# trackuino_sensor_mk2_chip.net
KiCad netlist of a schematic drawn in EAGLE
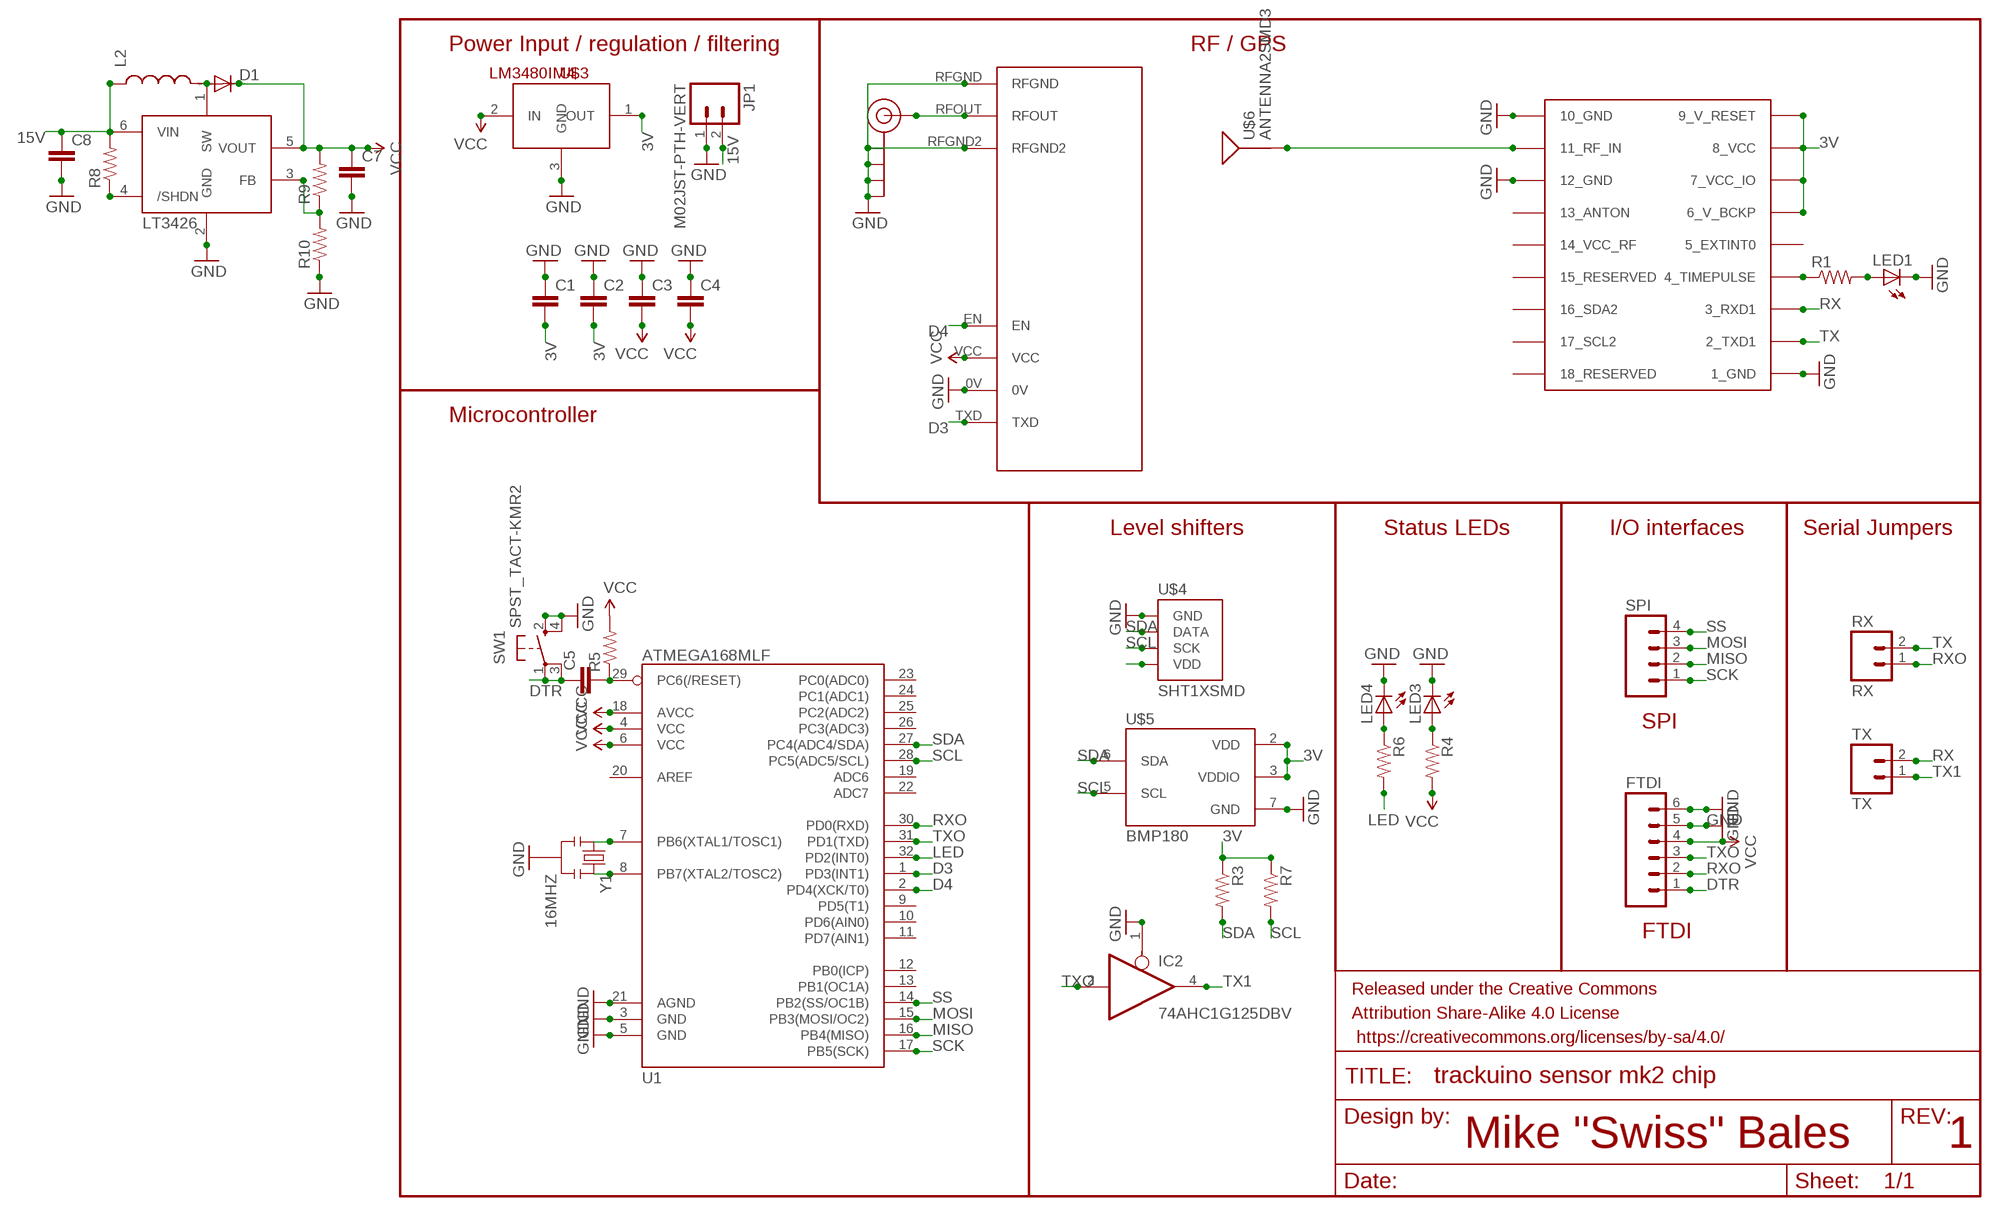
[diagram p0: schematic, sheet 1]

(export (version "E")
  (design (tool "Eeschema 10.0.6"))
  (components
    (comp (ref "C1")
      (value "CAP0805")
      (footprint "eagle-import:0805")
      (libsource (lib "eagle-import") (part "CAP0805"))
    )
    (comp (ref "C2")
      (value "CAP0805")
      (footprint "eagle-import:0805")
      (libsource (lib "eagle-import") (part "CAP0805"))
    )
    (comp (ref "C3")
      (value "CAP0805")
      (footprint "eagle-import:0805")
      (libsource (lib "eagle-import") (part "CAP0805"))
    )
    (comp (ref "C4")
      (value "CAP0805")
      (footprint "eagle-import:0805")
      (libsource (lib "eagle-import") (part "CAP0805"))
    )
    (comp (ref "C5")
      (value "CAP0805")
      (footprint "eagle-import:0805")
      (libsource (lib "eagle-import") (part "CAP0805"))
    )
    (comp (ref "C7")
      (value "CAP0805")
      (footprint "eagle-import:0805")
      (libsource (lib "eagle-import") (part "CAP0805"))
    )
    (comp (ref "C8")
      (value "CAP0805")
      (footprint "eagle-import:0805")
      (libsource (lib "eagle-import") (part "CAP0805"))
    )
    (comp (ref "D1")
      (value "DIODE-SOD123")
      (footprint "eagle-import:SOD123")
      (libsource (lib "eagle-import") (part "DIODE-SOD123"))
    )
    (comp (ref "FRAME1")
      (value "FRAME-LETTER")
      (footprint "eagle-import:CREATIVE_COMMONS")
      (libsource (lib "eagle-import") (part "FRAME-LETTER"))
    )
    (comp (ref "FTDI")
      (value "M06NO_SILK_FEMALE_PTH")
      (footprint "eagle-import:1X06_NO_SILK")
      (libsource (lib "eagle-import") (part "M06NO_SILK_FEMALE_PTH"))
    )
    (comp (ref "IC2")
      (value "74AHC1G125DBV")
      (footprint "eagle-import:SOT23-5")
      (libsource (lib "eagle-import") (part "741G125DBVAHC"))
    )
    (comp (ref "J$1")
      (value "SMA_EDGE")
      (footprint "eagle-import:SMA-EDGE")
      (libsource (lib "eagle-import") (part "SMA_EDGE"))
    )
    (comp (ref "JP1")
      (value "M02JST-PTH-VERT")
      (footprint "eagle-import:JST-2-PTH-VERT")
      (libsource (lib "eagle-import") (part "M02JST-PTH-VERT"))
    )
    (comp (ref "L2")
      (value "INDUCTOR0805")
      (footprint "eagle-import:0805")
      (libsource (lib "eagle-import") (part "INDUCTOR0805"))
    )
    (comp (ref "LED1")
      (value "LEDCHIP-LED0805")
      (footprint "eagle-import:CHIP-LED0805")
      (libsource (lib "eagle-import") (part "LEDCHIP-LED0805"))
    )
    (comp (ref "LED3")
      (value "LEDCHIP-LED0805")
      (footprint "eagle-import:CHIP-LED0805")
      (libsource (lib "eagle-import") (part "LEDCHIP-LED0805"))
    )
    (comp (ref "LED4")
      (value "LEDCHIP-LED0805")
      (footprint "eagle-import:CHIP-LED0805")
      (libsource (lib "eagle-import") (part "LEDCHIP-LED0805"))
    )
    (comp (ref "R1")
      (value "RESISTOR0805-RES")
      (footprint "eagle-import:0805")
      (libsource (lib "eagle-import") (part "RESISTOR0805-RES"))
    )
    (comp (ref "R3")
      (value "RESISTOR0805-RES")
      (footprint "eagle-import:0805")
      (libsource (lib "eagle-import") (part "RESISTOR0805-RES"))
    )
    (comp (ref "R4")
      (value "RESISTOR0805-RES")
      (footprint "eagle-import:0805")
      (libsource (lib "eagle-import") (part "RESISTOR0805-RES"))
    )
    (comp (ref "R5")
      (value "RESISTOR0805-RES")
      (footprint "eagle-import:0805")
      (libsource (lib "eagle-import") (part "RESISTOR0805-RES"))
    )
    (comp (ref "R6")
      (value "RESISTOR0805-RES")
      (footprint "eagle-import:0805")
      (libsource (lib "eagle-import") (part "RESISTOR0805-RES"))
    )
    (comp (ref "R7")
      (value "RESISTOR0805-RES")
      (footprint "eagle-import:0805")
      (libsource (lib "eagle-import") (part "RESISTOR0805-RES"))
    )
    (comp (ref "R8")
      (value "RESISTOR0805-RES")
      (footprint "eagle-import:0805")
      (libsource (lib "eagle-import") (part "RESISTOR0805-RES"))
    )
    (comp (ref "R9")
      (value "RESISTOR0805-RES")
      (footprint "eagle-import:0805")
      (libsource (lib "eagle-import") (part "RESISTOR0805-RES"))
    )
    (comp (ref "R10")
      (value "RESISTOR0805-RES")
      (footprint "eagle-import:0805")
      (libsource (lib "eagle-import") (part "RESISTOR0805-RES"))
    )
    (comp (ref "RX")
      (value "RX")
      (footprint "eagle-import:1X02")
      (libsource (lib "eagle-import") (part "M02PTH"))
    )
    (comp (ref "SPI")
      (value "M041X04_NO_SILK")
      (footprint "eagle-import:1X04_NO_SILK")
      (libsource (lib "eagle-import") (part "M041X04_NO_SILK"))
    )
    (comp (ref "SW1")
      (value "SPST_TACT-KMR2")
      (footprint "eagle-import:KMR2")
      (libsource (lib "eagle-import") (part "SPST_TACT-KMR2"))
    )
    (comp (ref "TX")
      (value "TX")
      (footprint "eagle-import:1X02")
      (libsource (lib "eagle-import") (part "M02PTH"))
    )
    (comp (ref "U$1")
      (value "UBLOX_MAX")
      (footprint "eagle-import:UBLOX_MAX")
      (libsource (lib "eagle-import") (part "UBLOX_MAX"))
    )
    (comp (ref "U$2")
      (value "RADIOMETRIX-HX1")
      (footprint "eagle-import:RADIOMETRIX-HX1")
      (libsource (lib "eagle-import") (part "RADIOMETRIX-HX1"))
    )
    (comp (ref "U$3")
      (value "LM3480IM4")
      (footprint "eagle-import:SOT23-3")
      (libsource (lib "eagle-import") (part "LM3480IM4"))
    )
    (comp (ref "U$4")
      (value "SHT1XSMD")
      (footprint "eagle-import:SHT1X")
      (libsource (lib "eagle-import") (part "SHT1XSMD"))
    )
    (comp (ref "U$5")
      (value "BMP180")
      (footprint "eagle-import:BMP180")
      (libsource (lib "eagle-import") (part "BMP180"))
    )
    (comp (ref "U$6")
      (value "ANTENNA2SMD3")
      (footprint "eagle-import:ANTENNA-CHIP4")
      (libsource (lib "eagle-import") (part "ANTENNA2SMD3"))
    )
    (comp (ref "U$7")
      (value "LT3426")
      (footprint "eagle-import:SOT23-6")
      (libsource (lib "eagle-import") (part "LT3426"))
    )
    (comp (ref "U1")
      (value "ATMEGA168MLF")
      (footprint "eagle-import:MLF32")
      (libsource (lib "eagle-import") (part "ATMEGA168MLF"))
    )
    (comp (ref "Y1")
      (value "16MHZ")
      (footprint "eagle-import:RESONATOR-SMD")
      (libsource (lib "eagle-import") (part "RESONATOR16MHZ"))
    )
  )
  (nets
    (net (code "1") (name "/3V") (class "Default")
      (node (ref "C1") (pin "2") (pinfunction "2_2") (pintype "passive"))
      (node (ref "C2") (pin "2") (pinfunction "2_2") (pintype "passive"))
      (node (ref "R3") (pin "1") (pinfunction "1_1") (pintype "passive"))
      (node (ref "R7") (pin "1") (pinfunction "1_1") (pintype "passive"))
      (node (ref "U$1") (pin "6_V_BCKP") (pinfunction "6_V_BCKP_6_V_BCKP") (pintype "bidirectional"))
      (node (ref "U$1") (pin "7_VCC_IO") (pinfunction "7_VCC_IO_7_VCC_IO") (pintype "power_in"))
      (node (ref "U$1") (pin "8_VCC") (pinfunction "8_VCC_8_VCC") (pintype "power_in"))
      (node (ref "U$1") (pin "9_V_RESET") (pinfunction "9_V_RESET_9_V_RESET") (pintype "power_in"))
      (node (ref "U$3") (pin "1") (pinfunction "OUT_1") (pintype "bidirectional"))
      (node (ref "U$4") (pin "4") (pinfunction "VDD_4") (pintype "power_in"))
      (node (ref "U$5") (pin "2") (pinfunction "VDD_2") (pintype "power_in"))
      (node (ref "U$5") (pin "3") (pinfunction "VDDIO_3") (pintype "power_in"))
    )
    (net (code "2") (name "/15V") (class "Default")
      (node (ref "C8") (pin "1") (pinfunction "1_1") (pintype "passive"))
      (node (ref "JP1") (pin "2") (pinfunction "2_2") (pintype "passive"))
      (node (ref "L2") (pin "1") (pinfunction "1_1") (pintype "passive"))
      (node (ref "R8") (pin "2") (pinfunction "2_2") (pintype "passive"))
      (node (ref "U$7") (pin "6") (pinfunction "VIN_6") (pintype "input"))
    )
    (net (code "3") (name "/D3") (class "Default")
      (node (ref "U$2") (pin "TXD") (pinfunction "TXD_TXD") (pintype "bidirectional"))
      (node (ref "U1") (pin "1") (pinfunction "PD3(INT1)_1") (pintype "bidirectional"))
    )
    (net (code "4") (name "/D4") (class "Default")
      (node (ref "U$2") (pin "EN") (pinfunction "EN_EN") (pintype "bidirectional"))
      (node (ref "U1") (pin "2") (pinfunction "PD4(XCK/T0)_2") (pintype "bidirectional"))
    )
    (net (code "5") (name "/DTR") (class "Default")
      (node (ref "C5") (pin "1") (pinfunction "1_1") (pintype "passive"))
      (node (ref "FTDI") (pin "1") (pinfunction "1_1") (pintype "passive"))
      (node (ref "SW1") (pin "1") (pinfunction "P_1") (pintype "passive"))
      (node (ref "SW1") (pin "3") (pinfunction "P1_3") (pintype "passive"))
    )
    (net (code "6") (name "/LED") (class "Default")
      (node (ref "R6") (pin "2") (pinfunction "2_2") (pintype "passive"))
      (node (ref "U1") (pin "32") (pinfunction "PD2(INT0)_32") (pintype "bidirectional"))
    )
    (net (code "7") (name "/MISO") (class "Default")
      (node (ref "SPI") (pin "2") (pinfunction "2_2") (pintype "passive"))
      (node (ref "U1") (pin "16") (pinfunction "PB4(MISO)_16") (pintype "bidirectional"))
    )
    (net (code "8") (name "/MOSI") (class "Default")
      (node (ref "SPI") (pin "3") (pinfunction "3_3") (pintype "passive"))
      (node (ref "U1") (pin "15") (pinfunction "PB3(MOSI/OC2)_15") (pintype "bidirectional"))
    )
    (net (code "9") (name "/RX") (class "Default")
      (node (ref "TX") (pin "2") (pinfunction "2_2") (pintype "passive"))
      (node (ref "U$1") (pin "3_RXD1") (pinfunction "3_RXD1_3_RXD1") (pintype "bidirectional"))
    )
    (net (code "10") (name "/RXO") (class "Default")
      (node (ref "FTDI") (pin "2") (pinfunction "2_2") (pintype "passive"))
      (node (ref "RX") (pin "1") (pinfunction "1_1") (pintype "passive"))
      (node (ref "U1") (pin "30") (pinfunction "PD0(RXD)_30") (pintype "bidirectional"))
    )
    (net (code "11") (name "/SCK") (class "Default")
      (node (ref "SPI") (pin "1") (pinfunction "1_1") (pintype "passive"))
      (node (ref "U1") (pin "17") (pinfunction "PB5(SCK)_17") (pintype "bidirectional"))
    )
    (net (code "12") (name "/SCL") (class "Default")
      (node (ref "R7") (pin "2") (pinfunction "2_2") (pintype "passive"))
      (node (ref "U$4") (pin "3") (pinfunction "SCK_3") (pintype "input"))
      (node (ref "U$5") (pin "5") (pinfunction "SCL_5") (pintype "input"))
      (node (ref "U1") (pin "28") (pinfunction "PC5(ADC5/SCL)_28") (pintype "bidirectional"))
    )
    (net (code "13") (name "/SDA") (class "Default")
      (node (ref "R3") (pin "2") (pinfunction "2_2") (pintype "passive"))
      (node (ref "U$4") (pin "2") (pinfunction "DATA_2") (pintype "bidirectional"))
      (node (ref "U$5") (pin "6") (pinfunction "SDA_6") (pintype "bidirectional"))
      (node (ref "U1") (pin "27") (pinfunction "PC4(ADC4/SDA)_27") (pintype "bidirectional"))
    )
    (net (code "14") (name "/SS") (class "Default")
      (node (ref "SPI") (pin "4") (pinfunction "4_4") (pintype "passive"))
      (node (ref "U1") (pin "14") (pinfunction "PB2(SS/OC1B)_14") (pintype "bidirectional"))
    )
    (net (code "15") (name "/TX") (class "Default")
      (node (ref "RX") (pin "2") (pinfunction "2_2") (pintype "passive"))
      (node (ref "U$1") (pin "2_TXD1") (pinfunction "2_TXD1_2_TXD1") (pintype "bidirectional"))
    )
    (net (code "16") (name "/TX1") (class "Default")
      (node (ref "IC2") (pin "4") (pinfunction "O_4") (pintype "tri_state"))
      (node (ref "TX") (pin "1") (pinfunction "1_1") (pintype "passive"))
    )
    (net (code "17") (name "/TXO") (class "Default")
      (node (ref "FTDI") (pin "3") (pinfunction "3_3") (pintype "passive"))
      (node (ref "IC2") (pin "2") (pinfunction "I_2") (pintype "input"))
      (node (ref "U1") (pin "31") (pinfunction "PD1(TXD)_31") (pintype "bidirectional"))
    )
    (net (code "18") (name "GND") (class "Default")
      (node (ref "C1") (pin "1") (pinfunction "1_1") (pintype "passive"))
      (node (ref "C2") (pin "1") (pinfunction "1_1") (pintype "passive"))
      (node (ref "C3") (pin "1") (pinfunction "1_1") (pintype "passive"))
      (node (ref "C4") (pin "1") (pinfunction "1_1") (pintype "passive"))
      (node (ref "C7") (pin "2") (pinfunction "2_2") (pintype "passive"))
      (node (ref "C8") (pin "2") (pinfunction "2_2") (pintype "passive"))
      (node (ref "FTDI") (pin "5") (pinfunction "5_5") (pintype "passive"))
      (node (ref "FTDI") (pin "6") (pinfunction "6_6") (pintype "passive"))
      (node (ref "IC2") (pin "1") (pinfunction "OE_1") (pintype "input"))
      (node (ref "J$1") (pin "GND@0") (pinfunction "GND_GND@0") (pintype "bidirectional"))
      (node (ref "J$1") (pin "GND@1") (pinfunction "GND_GND@1") (pintype "bidirectional"))
      (node (ref "J$1") (pin "GND@2") (pinfunction "GND_GND@2") (pintype "bidirectional"))
      (node (ref "J$1") (pin "GND@3") (pinfunction "GND_GND@3") (pintype "bidirectional"))
      (node (ref "JP1") (pin "1") (pinfunction "1_1") (pintype "passive"))
      (node (ref "LED1") (pin "C") (pinfunction "C_C") (pintype "passive"))
      (node (ref "LED3") (pin "C") (pinfunction "C_C") (pintype "passive"))
      (node (ref "LED4") (pin "C") (pinfunction "C_C") (pintype "passive"))
      (node (ref "R10") (pin "1") (pinfunction "1_1") (pintype "passive"))
      (node (ref "SW1") (pin "2") (pinfunction "S_2") (pintype "passive"))
      (node (ref "SW1") (pin "4") (pinfunction "S1_4") (pintype "passive"))
      (node (ref "U$1") (pin "10_GND") (pinfunction "10_GND_10_GND") (pintype "power_in"))
      (node (ref "U$1") (pin "12_GND") (pinfunction "12_GND_12_GND") (pintype "power_in"))
      (node (ref "U$1") (pin "1_GND") (pinfunction "1_GND_1_GND") (pintype "power_in"))
      (node (ref "U$2") (pin "0V") (pinfunction "0V_0V") (pintype "bidirectional"))
      (node (ref "U$2") (pin "RFGND") (pinfunction "RFGND_RFGND") (pintype "bidirectional"))
      (node (ref "U$2") (pin "RFGND2") (pinfunction "RFGND2_RFGND2") (pintype "bidirectional"))
      (node (ref "U$3") (pin "3") (pinfunction "GND_3") (pintype "bidirectional"))
      (node (ref "U$4") (pin "1") (pinfunction "GND_1") (pintype "power_in"))
      (node (ref "U$5") (pin "7") (pinfunction "GND_7") (pintype "power_in"))
      (node (ref "U$7") (pin "2") (pinfunction "GND_2") (pintype "power_in"))
      (node (ref "U1") (pin "21") (pinfunction "AGND_21") (pintype "bidirectional"))
      (node (ref "U1") (pin "3") (pinfunction "GND_3") (pintype "bidirectional"))
      (node (ref "U1") (pin "5") (pinfunction "GND_5") (pintype "bidirectional"))
      (node (ref "Y1") (pin "2") (pinfunction "2_2") (pintype "passive"))
    )
    (net (code "19") (name "Net-(J$1-SIGNAL)") (class "Default")
      (node (ref "J$1") (pin "SIG") (pinfunction "SIGNAL_SIG") (pintype "bidirectional"))
      (node (ref "U$2") (pin "RFOUT") (pinfunction "RFOUT_RFOUT") (pintype "bidirectional"))
    )
    (net (code "20") (name "Net-(LED1-PadA)") (class "Default")
      (node (ref "LED1") (pin "A") (pinfunction "A_A") (pintype "passive"))
      (node (ref "R1") (pin "2") (pinfunction "2_2") (pintype "passive"))
    )
    (net (code "21") (name "Net-(LED3-PadA)") (class "Default")
      (node (ref "LED3") (pin "A") (pinfunction "A_A") (pintype "passive"))
      (node (ref "R4") (pin "1") (pinfunction "1_1") (pintype "passive"))
    )
    (net (code "22") (name "Net-(LED4-PadA)") (class "Default")
      (node (ref "LED4") (pin "A") (pinfunction "A_A") (pintype "passive"))
      (node (ref "R6") (pin "1") (pinfunction "1_1") (pintype "passive"))
    )
    (net (code "23") (name "Net-(R1-Pad1)") (class "Default")
      (node (ref "R1") (pin "1") (pinfunction "1_1") (pintype "passive"))
      (node (ref "U$1") (pin "4_TIMEPULSE") (pinfunction "4_TIMEPULSE_4_TIMEPULSE") (pintype "bidirectional"))
    )
    (net (code "24") (name "Net-(U$6-SIGNAL)") (class "Default")
      (node (ref "U$1") (pin "11_RF_IN") (pinfunction "11_RF_IN_11_RF_IN") (pintype "bidirectional"))
      (node (ref "U$6") (pin "SIG") (pinfunction "SIGNAL_SIG") (pintype "bidirectional"))
    )
    (net (code "25") (name "Net-(U$7-FB)") (class "Default")
      (node (ref "R10") (pin "2") (pinfunction "2_2") (pintype "passive"))
      (node (ref "R9") (pin "1") (pinfunction "1_1") (pintype "passive"))
      (node (ref "U$7") (pin "3") (pinfunction "FB_3") (pintype "input"))
    )
    (net (code "26") (name "Net-(U$7-SW)") (class "Default")
      (node (ref "D1") (pin "A") (pinfunction "A_A") (pintype "passive"))
      (node (ref "L2") (pin "2") (pinfunction "2_2") (pintype "passive"))
      (node (ref "U$7") (pin "1") (pinfunction "SW_1") (pintype "output"))
    )
    (net (code "27") (name "Net-(U$7-{slash}SHDN)") (class "Default")
      (node (ref "R8") (pin "1") (pinfunction "1_1") (pintype "passive"))
      (node (ref "U$7") (pin "4") (pinfunction "/SHDN_4") (pintype "input"))
    )
    (net (code "28") (name "Net-(U1-PB6(XTAL1{slash}TOSC1))") (class "Default")
      (node (ref "U1") (pin "7") (pinfunction "PB6(XTAL1/TOSC1)_7") (pintype "bidirectional"))
      (node (ref "Y1") (pin "1") (pinfunction "1_1") (pintype "passive"))
    )
    (net (code "29") (name "Net-(U1-PB7(XTAL2{slash}TOSC2))") (class "Default")
      (node (ref "U1") (pin "8") (pinfunction "PB7(XTAL2/TOSC2)_8") (pintype "bidirectional"))
      (node (ref "Y1") (pin "3") (pinfunction "3_3") (pintype "passive"))
    )
    (net (code "30") (name "Net-(U1-PC6({slash}RESET))") (class "Default")
      (node (ref "C5") (pin "2") (pinfunction "2_2") (pintype "passive"))
      (node (ref "R5") (pin "1") (pinfunction "1_1") (pintype "passive"))
      (node (ref "U1") (pin "29") (pinfunction "PC6(/RESET)_29") (pintype "bidirectional"))
    )
    (net (code "31") (name "VCC") (class "Default")
      (node (ref "C3") (pin "2") (pinfunction "2_2") (pintype "passive"))
      (node (ref "C4") (pin "2") (pinfunction "2_2") (pintype "passive"))
      (node (ref "C7") (pin "1") (pinfunction "1_1") (pintype "passive"))
      (node (ref "D1") (pin "C") (pinfunction "C_C") (pintype "passive"))
      (node (ref "FTDI") (pin "4") (pinfunction "4_4") (pintype "passive"))
      (node (ref "R4") (pin "2") (pinfunction "2_2") (pintype "passive"))
      (node (ref "R5") (pin "2") (pinfunction "2_2") (pintype "passive"))
      (node (ref "R9") (pin "2") (pinfunction "2_2") (pintype "passive"))
      (node (ref "U$2") (pin "VCC") (pinfunction "VCC_VCC") (pintype "bidirectional"))
      (node (ref "U$3") (pin "2") (pinfunction "IN_2") (pintype "bidirectional"))
      (node (ref "U$7") (pin "5") (pinfunction "VOUT_5") (pintype "output"))
      (node (ref "U1") (pin "18") (pinfunction "AVCC_18") (pintype "bidirectional"))
      (node (ref "U1") (pin "4") (pinfunction "VCC_4") (pintype "bidirectional"))
      (node (ref "U1") (pin "6") (pinfunction "VCC_6") (pintype "bidirectional"))
    )
    (net (code "32") (name "unconnected-(U$1-Pad5_EXTINT0)") (class "Default")
      (node (ref "U$1") (pin "5_EXTINT0") (pinfunction "5_EXTINT0_5_EXTINT0") (pintype "bidirectional"))
    )
    (net (code "33") (name "unconnected-(U$1-Pad13_ANTON)") (class "Default")
      (node (ref "U$1") (pin "13_ANTON") (pinfunction "13_ANTON_13_ANTON") (pintype "bidirectional"))
    )
    (net (code "34") (name "unconnected-(U$1-Pad14_VCC_RF)") (class "Default")
      (node (ref "U$1") (pin "14_VCC_RF") (pinfunction "14_VCC_RF_14_VCC_RF") (pintype "bidirectional"))
    )
    (net (code "35") (name "unconnected-(U$1-Pad15_RESERVED)") (class "Default")
      (node (ref "U$1") (pin "15_RESERVED") (pinfunction "15_RESERVED_15_RESERVED") (pintype "bidirectional"))
    )
    (net (code "36") (name "unconnected-(U$1-Pad16_SDA2)") (class "Default")
      (node (ref "U$1") (pin "16_SDA2") (pinfunction "16_SDA2_16_SDA2") (pintype "bidirectional"))
    )
    (net (code "37") (name "unconnected-(U$1-Pad17_SCL2)") (class "Default")
      (node (ref "U$1") (pin "17_SCL2") (pinfunction "17_SCL2_17_SCL2") (pintype "bidirectional"))
    )
    (net (code "38") (name "unconnected-(U$1-Pad18_RESERVED)") (class "Default")
      (node (ref "U$1") (pin "18_RESERVED") (pinfunction "18_RESERVED_18_RESERVED") (pintype "bidirectional"))
    )
    (net (code "39") (name "unconnected-(U1-ADC6-Pad19)") (class "Default")
      (node (ref "U1") (pin "19") (pinfunction "ADC6_19") (pintype "bidirectional"))
    )
    (net (code "40") (name "unconnected-(U1-ADC7-Pad22)") (class "Default")
      (node (ref "U1") (pin "22") (pinfunction "ADC7_22") (pintype "bidirectional"))
    )
    (net (code "41") (name "unconnected-(U1-AREF-Pad20)") (class "Default")
      (node (ref "U1") (pin "20") (pinfunction "AREF_20") (pintype "bidirectional"))
    )
    (net (code "42") (name "unconnected-(U1-PB0(ICP)-Pad12)") (class "Default")
      (node (ref "U1") (pin "12") (pinfunction "PB0(ICP)_12") (pintype "bidirectional"))
    )
    (net (code "43") (name "unconnected-(U1-PB1(OC1A)-Pad13)") (class "Default")
      (node (ref "U1") (pin "13") (pinfunction "PB1(OC1A)_13") (pintype "bidirectional"))
    )
    (net (code "44") (name "unconnected-(U1-PC0(ADC0)-Pad23)") (class "Default")
      (node (ref "U1") (pin "23") (pinfunction "PC0(ADC0)_23") (pintype "bidirectional"))
    )
    (net (code "45") (name "unconnected-(U1-PC1(ADC1)-Pad24)") (class "Default")
      (node (ref "U1") (pin "24") (pinfunction "PC1(ADC1)_24") (pintype "bidirectional"))
    )
    (net (code "46") (name "unconnected-(U1-PC2(ADC2)-Pad25)") (class "Default")
      (node (ref "U1") (pin "25") (pinfunction "PC2(ADC2)_25") (pintype "bidirectional"))
    )
    (net (code "47") (name "unconnected-(U1-PC3(ADC3)-Pad26)") (class "Default")
      (node (ref "U1") (pin "26") (pinfunction "PC3(ADC3)_26") (pintype "bidirectional"))
    )
    (net (code "48") (name "unconnected-(U1-PD5(T1)-Pad9)") (class "Default")
      (node (ref "U1") (pin "9") (pinfunction "PD5(T1)_9") (pintype "bidirectional"))
    )
    (net (code "49") (name "unconnected-(U1-PD6(AIN0)-Pad10)") (class "Default")
      (node (ref "U1") (pin "10") (pinfunction "PD6(AIN0)_10") (pintype "bidirectional"))
    )
    (net (code "50") (name "unconnected-(U1-PD7(AIN1)-Pad11)") (class "Default")
      (node (ref "U1") (pin "11") (pinfunction "PD7(AIN1)_11") (pintype "bidirectional"))
    )
  )
)
